# Adafruit_Sparkle_Motion_Stick.net
KiCad netlist of a schematic drawn in EAGLE
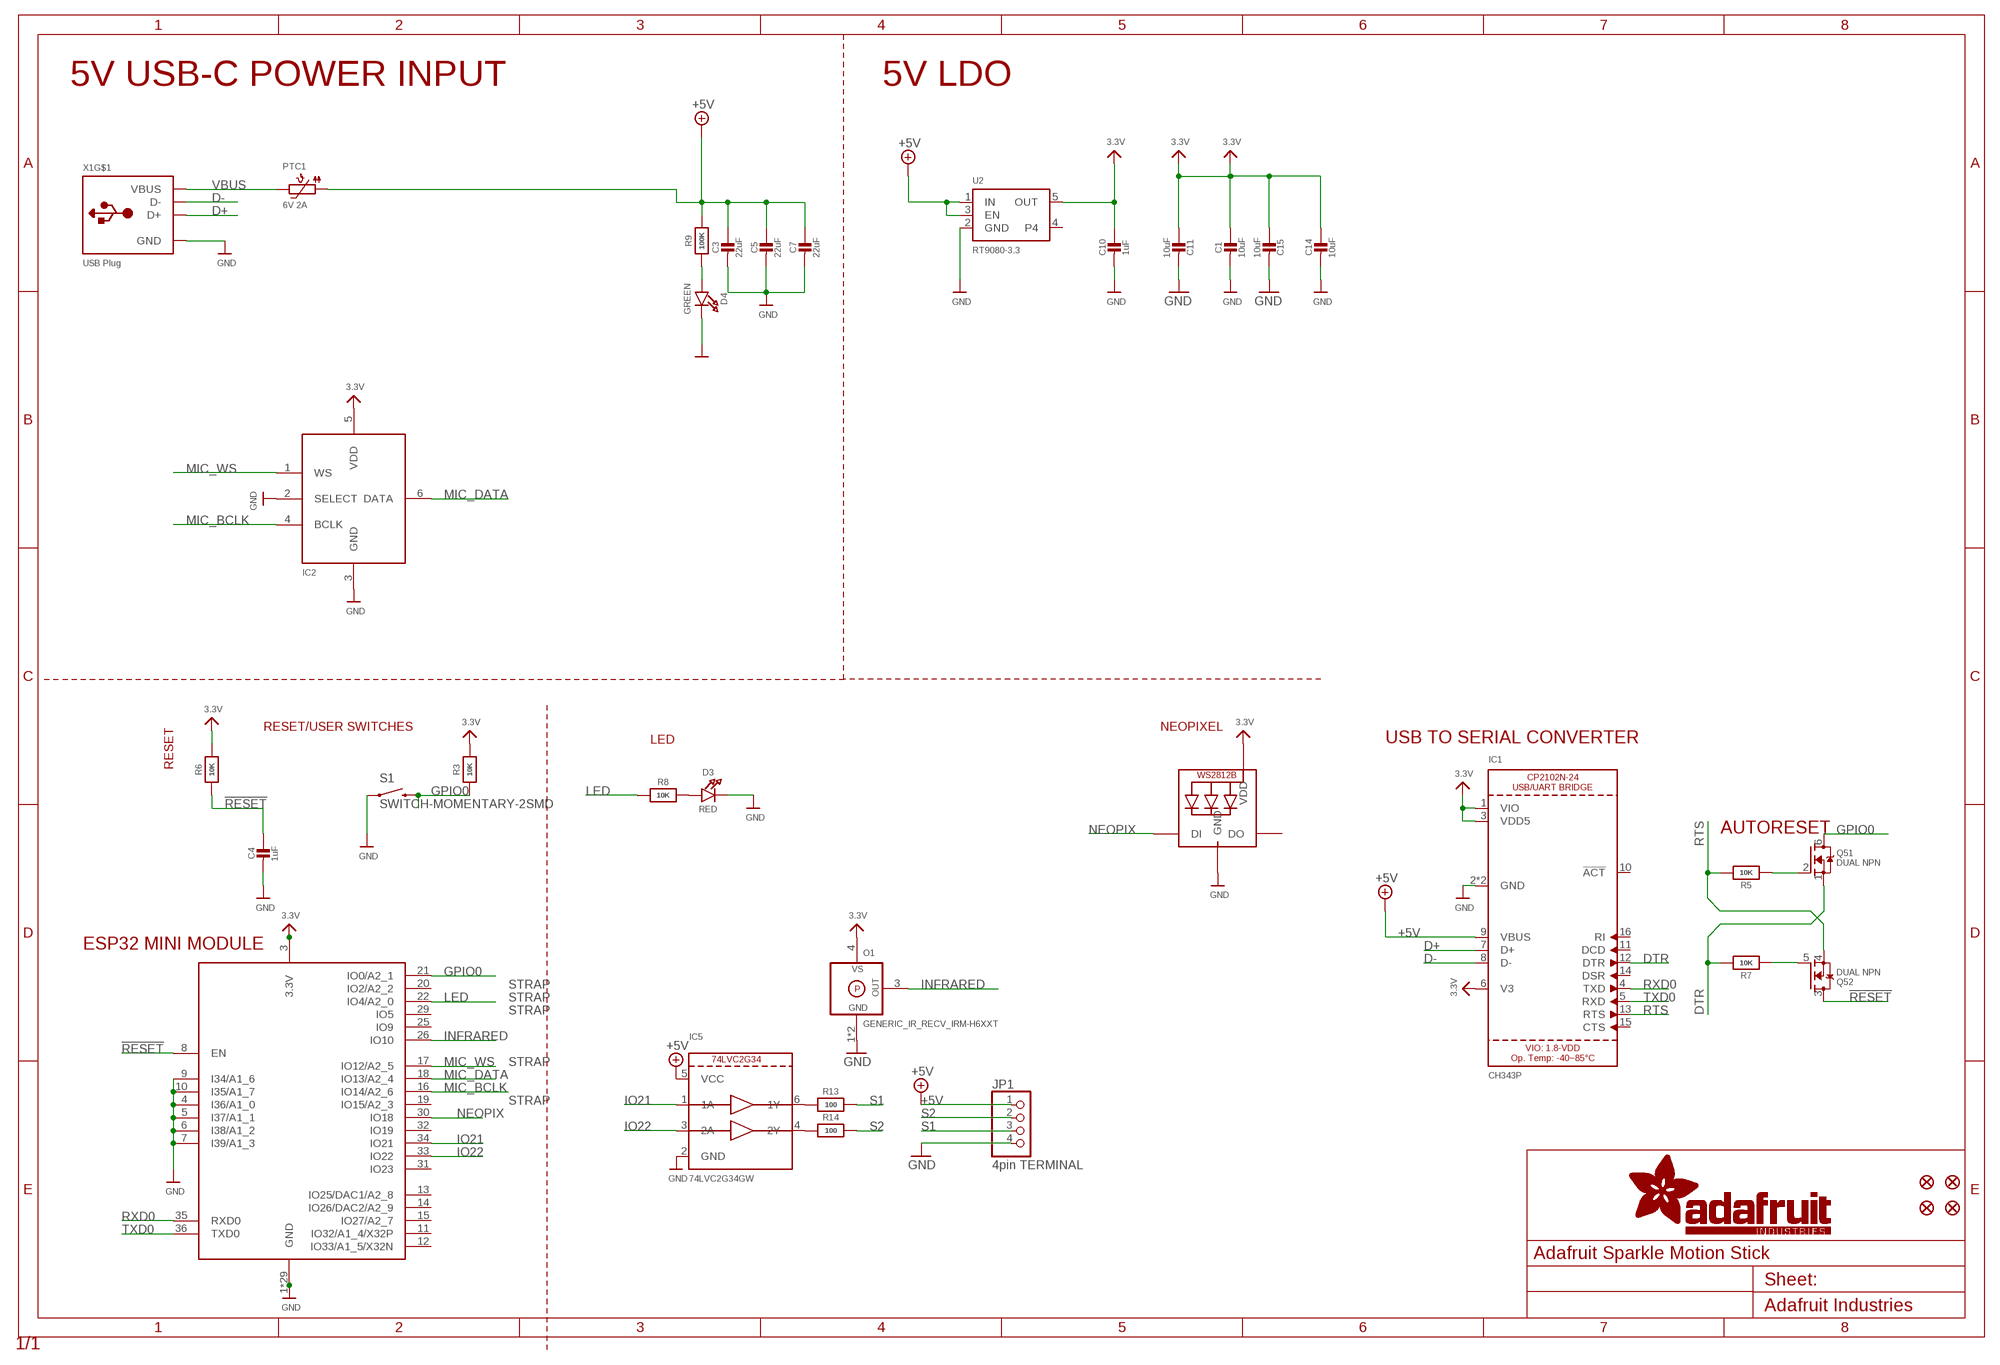
[diagram p0: schematic, sheet 1]

(export (version "E")
  (design (tool "Eeschema 10.0.6"))
  (components
    (comp (ref "C1")
      (value "10uF")
      (footprint "eagle-import:0805-NO")
      (libsource (lib "eagle-import") (part "CAP_CERAMIC0805-NOOUTLINE"))
    )
    (comp (ref "C3")
      (value "22uF")
      (footprint "eagle-import:0805-NO")
      (libsource (lib "eagle-import") (part "CAP_CERAMIC0805-NOOUTLINE"))
    )
    (comp (ref "C4")
      (value "1uF")
      (footprint "eagle-import:0603-NO")
      (libsource (lib "eagle-import") (part "CAP_CERAMIC0603_NO"))
    )
    (comp (ref "C5")
      (value "22uF")
      (footprint "eagle-import:0805-NO")
      (libsource (lib "eagle-import") (part "CAP_CERAMIC0805-NOOUTLINE"))
    )
    (comp (ref "C7")
      (value "22uF")
      (footprint "eagle-import:0805-NO")
      (libsource (lib "eagle-import") (part "CAP_CERAMIC0805-NOOUTLINE"))
    )
    (comp (ref "C10")
      (value "1uF")
      (footprint "eagle-import:0603-NO")
      (libsource (lib "eagle-import") (part "CAP_CERAMIC0603_NO"))
    )
    (comp (ref "C11")
      (value "10uF")
      (footprint "eagle-import:0805-NO")
      (libsource (lib "eagle-import") (part "CAP_CERAMIC0805-NOOUTLINE"))
    )
    (comp (ref "C14")
      (value "10uF")
      (footprint "eagle-import:0805-NO")
      (libsource (lib "eagle-import") (part "CAP_CERAMIC0805-NOOUTLINE"))
    )
    (comp (ref "C15")
      (value "10uF")
      (footprint "eagle-import:0805-NO")
      (libsource (lib "eagle-import") (part "CAP_CERAMIC0805-NOOUTLINE"))
    )
    (comp (ref "D3")
      (value "RED")
      (footprint "eagle-import:CHIPLED_0603_NOOUTLINE")
      (libsource (lib "eagle-import") (part "LED0603_NOOUTLINE"))
    )
    (comp (ref "D4")
      (value "GREEN")
      (footprint "eagle-import:CHIPLED_0603_NOOUTLINE")
      (libsource (lib "eagle-import") (part "LED0603_NOOUTLINE"))
    )
    (comp (ref "IC1")
      (value "CH343P")
      (footprint "eagle-import:QFN16_3MM")
      (libsource (lib "eagle-import") (part "CH343P"))
    )
    (comp (ref "IC2")
      (value "ICS-43434")
      (footprint "eagle-import:SPH0645LM4H")
      (libsource (lib "eagle-import") (part "MIC_I2S_SPH0645"))
    )
    (comp (ref "IC5")
      (value "74LVC2G34GW")
      (footprint "eagle-import:SC70-6L")
      (libsource (lib "eagle-import") (part "74LVC2G34GW"))
    )
    (comp (ref "JP1")
      (value "4pin TERMINAL")
      (footprint "eagle-import:1X04_2.54MMTERMINAL")
      (libsource (lib "eagle-import") (part "HEADER-1X4_254MMTERM"))
    )
    (comp (ref "LED1")
      (value "WS2812B_SK6805_1515")
      (footprint "eagle-import:SK6805_1515")
      (libsource (lib "eagle-import") (part "WS2812B_SK6805_1515"))
    )
    (comp (ref "O1")
      (value "GENERIC_IR_RECV_IRM-H6XXT")
      (footprint "eagle-import:IRM-H6XXT")
      (libsource (lib "eagle-import") (part "GENERIC_IR_RECV_IRM-H6XXT"))
    )
    (comp (ref "PTC1")
      (value "6V 2A")
      (footprint "eagle-import:0805-NO")
      (libsource (lib "eagle-import") (part "PTC_0805"))
    )
    (comp (ref "Q5")
      (value "DUAL NPN")
      (footprint "eagle-import:SOT363")
      (fields (field (name "JLC_ROTATION") "90"))
      (libsource (lib "eagle-import") (part "MOSFET-N_DUAL"))
    )
    (comp (ref "R3")
      (value "10K")
      (footprint "eagle-import:0603-NO")
      (libsource (lib "eagle-import") (part "RESISTOR_0603_NOOUT"))
    )
    (comp (ref "R5")
      (value "10K")
      (footprint "eagle-import:0603-NO")
      (libsource (lib "eagle-import") (part "RESISTOR_0603_NOOUT"))
    )
    (comp (ref "R6")
      (value "10K")
      (footprint "eagle-import:0603-NO")
      (libsource (lib "eagle-import") (part "RESISTOR_0603_NOOUT"))
    )
    (comp (ref "R7")
      (value "10K")
      (footprint "eagle-import:0603-NO")
      (libsource (lib "eagle-import") (part "RESISTOR_0603_NOOUT"))
    )
    (comp (ref "R8")
      (value "10K")
      (footprint "eagle-import:0603-NO")
      (libsource (lib "eagle-import") (part "RESISTOR_0603_NOOUT"))
    )
    (comp (ref "R9")
      (value "100K")
      (footprint "eagle-import:0603-NO")
      (libsource (lib "eagle-import") (part "RESISTOR_0603_NOOUT"))
    )
    (comp (ref "R13")
      (value "100")
      (footprint "eagle-import:0603-NO")
      (libsource (lib "eagle-import") (part "RESISTOR_0603_NOOUT"))
    )
    (comp (ref "R14")
      (value "100")
      (footprint "eagle-import:0603-NO")
      (libsource (lib "eagle-import") (part "RESISTOR_0603_NOOUT"))
    )
    (comp (ref "S1")
      (value "SWITCH-MOMENTARY-2SMD")
      (footprint "eagle-import:TACTILE_SWITCH_SMD")
      (libsource (lib "eagle-import") (part "SWITCH-MOMENTARY-2SMD"))
    )
    (comp (ref "U$23")
      (value "FIDUCIAL_0.5MM")
      (footprint "eagle-import:FIDUCIAL_0.5MM")
      (libsource (lib "eagle-import") (part "FIDUCIAL_0.5MM"))
    )
    (comp (ref "U$25")
      (value "FIDUCIAL_0.5MM")
      (footprint "eagle-import:FIDUCIAL_0.5MM")
      (libsource (lib "eagle-import") (part "FIDUCIAL_0.5MM"))
    )
    (comp (ref "U$34")
      (value "FIDUCIAL_0.5MM")
      (footprint "eagle-import:FIDUCIAL_0.5MM")
      (libsource (lib "eagle-import") (part "FIDUCIAL_0.5MM"))
    )
    (comp (ref "U$35")
      (value "FIDUCIAL_0.5MM")
      (footprint "eagle-import:FIDUCIAL_0.5MM")
      (libsource (lib "eagle-import") (part "FIDUCIAL_0.5MM"))
    )
    (comp (ref "U2")
      (value "RT9080-3.3")
      (footprint "eagle-import:SOT23-5")
      (fields (field (name "JLC_ROTATION") "0"))
      (libsource (lib "eagle-import") (part "VREG_SOT23-5"))
    )
    (comp (ref "X1")
      (value "USB Plug")
      (footprint "eagle-import:USB_A-UGO4DD")
      (libsource (lib "eagle-import") (part "USB_TYPEA_UG04DD"))
    )
    (comp (ref "X4")
      (value "ESP32-MINI-1")
      (footprint "eagle-import:ESP32-MINI-1")
      (libsource (lib "eagle-import") (part "ESP32-MINI-1"))
    )
  )
  (nets
    (net (code "1") (name "+5V") (class "Default")
      (node (ref "C3") (pin "1") (pinfunction "1_1") (pintype "passive"))
      (node (ref "C5") (pin "1") (pinfunction "1_1") (pintype "passive"))
      (node (ref "C7") (pin "1") (pinfunction "1_1") (pintype "passive"))
      (node (ref "IC1") (pin "9") (pinfunction "VBUS_9") (pintype "power_in"))
      (node (ref "IC5") (pin "5") (pinfunction "VCC_5") (pintype "power_in"))
      (node (ref "JP1") (pin "1") (pinfunction "1_1") (pintype "passive"))
      (node (ref "PTC1") (pin "1") (pinfunction "1_1") (pintype "passive"))
      (node (ref "R9") (pin "2") (pinfunction "2_2") (pintype "passive"))
      (node (ref "U2") (pin "1") (pinfunction "IN_1") (pintype "power_in"))
      (node (ref "U2") (pin "3") (pinfunction "EN_3") (pintype "input"))
    )
    (net (code "2") (name "/D+") (class "Default")
      (node (ref "IC1") (pin "7") (pinfunction "D+_7") (pintype "bidirectional"))
      (node (ref "X1") (pin "D+") (pinfunction "D+_D+") (pintype "bidirectional"))
    )
    (net (code "3") (name "/D-") (class "Default")
      (node (ref "IC1") (pin "8") (pinfunction "D-_8") (pintype "bidirectional"))
      (node (ref "X1") (pin "D-") (pinfunction "D-_D-") (pintype "bidirectional"))
    )
    (net (code "4") (name "/DTR") (class "Default")
      (node (ref "IC1") (pin "12") (pinfunction "DTR_12") (pintype "output"))
      (node (ref "Q5") (pin "1") (pinfunction "S_1") (pintype "bidirectional"))
      (node (ref "R7") (pin "2") (pinfunction "2_2") (pintype "passive"))
    )
    (net (code "5") (name "/GPIO0") (class "Default")
      (node (ref "Q5") (pin "6") (pinfunction "D_6") (pintype "bidirectional"))
      (node (ref "R3") (pin "1") (pinfunction "1_1") (pintype "passive"))
      (node (ref "S1") (pin "3") (pinfunction "2_3") (pintype "passive"))
      (node (ref "X4") (pin "21") (pinfunction "IO0/A2_1_21") (pintype "bidirectional"))
    )
    (net (code "6") (name "/INFRARED") (class "Default")
      (node (ref "O1") (pin "3") (pinfunction "OUT_3") (pintype "output"))
      (node (ref "X4") (pin "26") (pinfunction "IO10_26") (pintype "bidirectional"))
    )
    (net (code "7") (name "/IO21") (class "Default")
      (node (ref "IC5") (pin "1") (pinfunction "1A_1") (pintype "input"))
      (node (ref "X4") (pin "34") (pinfunction "IO21_34") (pintype "bidirectional"))
    )
    (net (code "8") (name "/IO22") (class "Default")
      (node (ref "IC5") (pin "3") (pinfunction "2A_3") (pintype "input"))
      (node (ref "X4") (pin "33") (pinfunction "IO22_33") (pintype "bidirectional"))
    )
    (net (code "9") (name "/LED") (class "Default")
      (node (ref "R8") (pin "1") (pinfunction "1_1") (pintype "passive"))
      (node (ref "X4") (pin "22") (pinfunction "IO4/A2_0_22") (pintype "bidirectional"))
    )
    (net (code "10") (name "/MIC_BCLK") (class "Default")
      (node (ref "IC2") (pin "4") (pinfunction "BCLK_4") (pintype "input"))
      (node (ref "X4") (pin "16") (pinfunction "IO14/A2_6_16") (pintype "bidirectional"))
    )
    (net (code "11") (name "/MIC_DATA") (class "Default")
      (node (ref "IC2") (pin "6") (pinfunction "DATA_6") (pintype "output"))
      (node (ref "X4") (pin "18") (pinfunction "IO13/A2_4_18") (pintype "bidirectional"))
    )
    (net (code "12") (name "/MIC_WS") (class "Default")
      (node (ref "IC2") (pin "1") (pinfunction "WS_1") (pintype "input"))
      (node (ref "X4") (pin "17") (pinfunction "IO12/A2_5_17") (pintype "bidirectional"))
    )
    (net (code "13") (name "/NEOPIX") (class "Default")
      (node (ref "LED1") (pin "1") (pinfunction "DI_1") (pintype "input"))
      (node (ref "X4") (pin "30") (pinfunction "IO18_30") (pintype "bidirectional"))
    )
    (net (code "14") (name "/RTS") (class "Default")
      (node (ref "IC1") (pin "13") (pinfunction "RTS_13") (pintype "output"))
      (node (ref "Q5") (pin "4") (pinfunction "S_4") (pintype "bidirectional"))
      (node (ref "R5") (pin "2") (pinfunction "2_2") (pintype "passive"))
    )
    (net (code "15") (name "/RXD0") (class "Default")
      (node (ref "IC1") (pin "4") (pinfunction "TXD_4") (pintype "output"))
      (node (ref "X4") (pin "35") (pinfunction "RXD0_35") (pintype "input"))
    )
    (net (code "16") (name "/S1") (class "Default")
      (node (ref "JP1") (pin "3") (pinfunction "3_3") (pintype "passive"))
      (node (ref "R13") (pin "2") (pinfunction "2_2") (pintype "passive"))
    )
    (net (code "17") (name "/S2") (class "Default")
      (node (ref "JP1") (pin "2") (pinfunction "2_2") (pintype "passive"))
      (node (ref "R14") (pin "2") (pinfunction "2_2") (pintype "passive"))
    )
    (net (code "18") (name "/TXD0") (class "Default")
      (node (ref "IC1") (pin "5") (pinfunction "RXD_5") (pintype "input"))
      (node (ref "X4") (pin "36") (pinfunction "TXD0_36") (pintype "output"))
    )
    (net (code "19") (name "/VBUS") (class "Default")
      (node (ref "PTC1") (pin "2") (pinfunction "2_2") (pintype "passive"))
      (node (ref "X1") (pin "VBUS") (pinfunction "VBUS_VBUS") (pintype "power_in"))
    )
    (net (code "20") (name "/~{RESET}") (class "Default")
      (node (ref "C4") (pin "1") (pinfunction "1_1") (pintype "passive"))
      (node (ref "Q5") (pin "3") (pinfunction "D_3") (pintype "bidirectional"))
      (node (ref "R6") (pin "1") (pinfunction "1_1") (pintype "passive"))
      (node (ref "X4") (pin "8") (pinfunction "EN_8") (pintype "input"))
    )
    (net (code "21") (name "3.3V") (class "Default")
      (node (ref "C1") (pin "1") (pinfunction "1_1") (pintype "passive"))
      (node (ref "C10") (pin "1") (pinfunction "1_1") (pintype "passive"))
      (node (ref "C11") (pin "1") (pinfunction "1_1") (pintype "passive"))
      (node (ref "C14") (pin "1") (pinfunction "1_1") (pintype "passive"))
      (node (ref "C15") (pin "1") (pinfunction "1_1") (pintype "passive"))
      (node (ref "IC1") (pin "1") (pinfunction "VIO_1") (pintype "power_in"))
      (node (ref "IC1") (pin "3") (pinfunction "VDD5_3") (pintype "power_in"))
      (node (ref "IC1") (pin "6") (pinfunction "V3_6") (pintype "passive"))
      (node (ref "IC2") (pin "5") (pinfunction "VDD_5") (pintype "power_in"))
      (node (ref "LED1") (pin "2") (pinfunction "VDD_2") (pintype "power_in"))
      (node (ref "O1") (pin "4") (pinfunction "VS_4") (pintype "power_in"))
      (node (ref "R3") (pin "2") (pinfunction "2_2") (pintype "passive"))
      (node (ref "R6") (pin "2") (pinfunction "2_2") (pintype "passive"))
      (node (ref "U2") (pin "5") (pinfunction "OUT_5") (pintype "power_in"))
      (node (ref "X4") (pin "3") (pinfunction "3.3V_3") (pintype "passive"))
    )
    (net (code "22") (name "GND") (class "Default")
      (node (ref "C1") (pin "2") (pinfunction "2_2") (pintype "passive"))
      (node (ref "C10") (pin "2") (pinfunction "2_2") (pintype "passive"))
      (node (ref "C11") (pin "2") (pinfunction "2_2") (pintype "passive"))
      (node (ref "C14") (pin "2") (pinfunction "2_2") (pintype "passive"))
      (node (ref "C15") (pin "2") (pinfunction "2_2") (pintype "passive"))
      (node (ref "C3") (pin "2") (pinfunction "2_2") (pintype "passive"))
      (node (ref "C4") (pin "2") (pinfunction "2_2") (pintype "passive"))
      (node (ref "C5") (pin "2") (pinfunction "2_2") (pintype "passive"))
      (node (ref "C7") (pin "2") (pinfunction "2_2") (pintype "passive"))
      (node (ref "D3") (pin "C") (pinfunction "C_C") (pintype "passive"))
      (node (ref "D4") (pin "C") (pinfunction "C_C") (pintype "passive"))
      (node (ref "IC1") (pin "2") (pinfunction "GND_2") (pintype "power_in"))
      (node (ref "IC1") (pin "THERMAL") (pinfunction "GND_THERMAL") (pintype "power_in"))
      (node (ref "IC2") (pin "2") (pinfunction "SELECT_2") (pintype "input"))
      (node (ref "IC2") (pin "3") (pinfunction "GND_3") (pintype "power_in"))
      (node (ref "IC5") (pin "2") (pinfunction "GND_2") (pintype "power_in"))
      (node (ref "JP1") (pin "4") (pinfunction "4_4") (pintype "passive"))
      (node (ref "LED1") (pin "4") (pinfunction "GND_4") (pintype "power_in"))
      (node (ref "O1") (pin "1") (pinfunction "GND_1") (pintype "power_in"))
      (node (ref "O1") (pin "2") (pinfunction "GND_2") (pintype "power_in"))
      (node (ref "S1") (pin "1") (pinfunction "1_1") (pintype "passive"))
      (node (ref "U2") (pin "2") (pinfunction "GND_2") (pintype "power_in"))
      (node (ref "X1") (pin "GND") (pinfunction "GND_GND") (pintype "power_in"))
      (node (ref "X4") (pin "1") (pinfunction "GND_1") (pintype "passive"))
      (node (ref "X4") (pin "10") (pinfunction "I35/A1_7_10") (pintype "input"))
      (node (ref "X4") (pin "2") (pinfunction "GND_2") (pintype "passive"))
      (node (ref "X4") (pin "27") (pinfunction "GND_27") (pintype "passive"))
      (node (ref "X4") (pin "38") (pinfunction "GND_38") (pintype "passive"))
      (node (ref "X4") (pin "39") (pinfunction "GND_39") (pintype "passive"))
      (node (ref "X4") (pin "4") (pinfunction "I36/A1_0_4") (pintype "input"))
      (node (ref "X4") (pin "40") (pinfunction "GND_40") (pintype "passive"))
      (node (ref "X4") (pin "41") (pinfunction "GND_41") (pintype "passive"))
      (node (ref "X4") (pin "42") (pinfunction "GND_42") (pintype "passive"))
      (node (ref "X4") (pin "43") (pinfunction "GND_43") (pintype "passive"))
      (node (ref "X4") (pin "44") (pinfunction "GND_44") (pintype "passive"))
      (node (ref "X4") (pin "45") (pinfunction "GND_45") (pintype "passive"))
      (node (ref "X4") (pin "46") (pinfunction "GND_46") (pintype "passive"))
      (node (ref "X4") (pin "47") (pinfunction "GND_47") (pintype "passive"))
      (node (ref "X4") (pin "48") (pinfunction "GND_48") (pintype "passive"))
      (node (ref "X4") (pin "49") (pinfunction "GND_49") (pintype "passive"))
      (node (ref "X4") (pin "5") (pinfunction "I37/A1_1_5") (pintype "input"))
      (node (ref "X4") (pin "50") (pinfunction "GND_50") (pintype "passive"))
      (node (ref "X4") (pin "51") (pinfunction "GND_51") (pintype "passive"))
      (node (ref "X4") (pin "52") (pinfunction "GND_52") (pintype "passive"))
      (node (ref "X4") (pin "53") (pinfunction "GND_53") (pintype "passive"))
      (node (ref "X4") (pin "54") (pinfunction "GND_54") (pintype "passive"))
      (node (ref "X4") (pin "55") (pinfunction "GND_55") (pintype "passive"))
      (node (ref "X4") (pin "56") (pinfunction "GND_56") (pintype "passive"))
      (node (ref "X4") (pin "57") (pinfunction "GND_57") (pintype "passive"))
      (node (ref "X4") (pin "58") (pinfunction "GND_58") (pintype "passive"))
      (node (ref "X4") (pin "59") (pinfunction "GND_59") (pintype "passive"))
      (node (ref "X4") (pin "6") (pinfunction "I38/A1_2_6") (pintype "input"))
      (node (ref "X4") (pin "60") (pinfunction "GND_60") (pintype "passive"))
      (node (ref "X4") (pin "61") (pinfunction "GND_61") (pintype "passive"))
      (node (ref "X4") (pin "62") (pinfunction "GND_62") (pintype "passive"))
      (node (ref "X4") (pin "63") (pinfunction "GND_63") (pintype "passive"))
      (node (ref "X4") (pin "7") (pinfunction "I39/A1_3_7") (pintype "input"))
      (node (ref "X4") (pin "9") (pinfunction "I34/A1_6_9") (pintype "input"))
    )
    (net (code "23") (name "Net-(D3-PadA)") (class "Default")
      (node (ref "D3") (pin "A") (pinfunction "A_A") (pintype "passive"))
      (node (ref "R8") (pin "2") (pinfunction "2_2") (pintype "passive"))
    )
    (net (code "24") (name "Net-(D4-PadA)") (class "Default")
      (node (ref "D4") (pin "A") (pinfunction "A_A") (pintype "passive"))
      (node (ref "R9") (pin "1") (pinfunction "1_1") (pintype "passive"))
    )
    (net (code "25") (name "Net-(IC5-1Y)") (class "Default")
      (node (ref "IC5") (pin "6") (pinfunction "1Y_6") (pintype "output"))
      (node (ref "R13") (pin "1") (pinfunction "1_1") (pintype "passive"))
    )
    (net (code "26") (name "Net-(IC5-2Y)") (class "Default")
      (node (ref "IC5") (pin "4") (pinfunction "2Y_4") (pintype "output"))
      (node (ref "R14") (pin "1") (pinfunction "1_1") (pintype "passive"))
    )
    (net (code "27") (name "Net-(Q5A-G)") (class "Default")
      (node (ref "Q5") (pin "2") (pinfunction "G_2") (pintype "bidirectional"))
      (node (ref "R5") (pin "1") (pinfunction "1_1") (pintype "passive"))
    )
    (net (code "28") (name "Net-(Q5B-G)") (class "Default")
      (node (ref "Q5") (pin "5") (pinfunction "G_5") (pintype "bidirectional"))
      (node (ref "R7") (pin "1") (pinfunction "1_1") (pintype "passive"))
    )
    (net (code "29") (name "unconnected-(IC1-CTS-Pad15)") (class "Default")
      (node (ref "IC1") (pin "15") (pinfunction "CTS_15") (pintype "input"))
    )
    (net (code "30") (name "unconnected-(IC1-DCD-Pad11)") (class "Default")
      (node (ref "IC1") (pin "11") (pinfunction "DCD_11") (pintype "input"))
    )
    (net (code "31") (name "unconnected-(IC1-DSR-Pad14)") (class "Default")
      (node (ref "IC1") (pin "14") (pinfunction "DSR_14") (pintype "input"))
    )
    (net (code "32") (name "unconnected-(IC1-RI-Pad16)") (class "Default")
      (node (ref "IC1") (pin "16") (pinfunction "RI_16") (pintype "input"))
    )
    (net (code "33") (name "unconnected-(IC1-~{ACT}-Pad10)") (class "Default")
      (node (ref "IC1") (pin "10") (pinfunction "~{ACT}_10") (pintype "bidirectional"))
    )
    (net (code "34") (name "unconnected-(LED1-DO-Pad3)") (class "Default")
      (node (ref "LED1") (pin "3") (pinfunction "DO_3") (pintype "output"))
    )
    (net (code "35") (name "unconnected-(U2-P4-Pad4)") (class "Default")
      (node (ref "U2") (pin "4") (pinfunction "P4_4") (pintype "bidirectional"))
    )
    (net (code "36") (name "unconnected-(X4-IO2{slash}A2_2-Pad20)") (class "Default")
      (node (ref "X4") (pin "20") (pinfunction "IO2/A2_2_20") (pintype "bidirectional"))
    )
    (net (code "37") (name "unconnected-(X4-IO5-Pad29)") (class "Default")
      (node (ref "X4") (pin "29") (pinfunction "IO5_29") (pintype "bidirectional"))
    )
    (net (code "38") (name "unconnected-(X4-IO9-Pad25)") (class "Default")
      (node (ref "X4") (pin "25") (pinfunction "IO9_25") (pintype "bidirectional"))
    )
    (net (code "39") (name "unconnected-(X4-IO15{slash}A2_3-Pad19)") (class "Default")
      (node (ref "X4") (pin "19") (pinfunction "IO15/A2_3_19") (pintype "bidirectional"))
    )
    (net (code "40") (name "unconnected-(X4-IO19-Pad32)") (class "Default")
      (node (ref "X4") (pin "32") (pinfunction "IO19_32") (pintype "bidirectional"))
    )
    (net (code "41") (name "unconnected-(X4-IO23-Pad31)") (class "Default")
      (node (ref "X4") (pin "31") (pinfunction "IO23_31") (pintype "bidirectional"))
    )
    (net (code "42") (name "unconnected-(X4-IO25{slash}DAC1{slash}A2_8-Pad13)") (class "Default")
      (node (ref "X4") (pin "13") (pinfunction "IO25/DAC1/A2_8_13") (pintype "bidirectional"))
    )
    (net (code "43") (name "unconnected-(X4-IO26{slash}DAC2{slash}A2_9-Pad14)") (class "Default")
      (node (ref "X4") (pin "14") (pinfunction "IO26/DAC2/A2_9_14") (pintype "bidirectional"))
    )
    (net (code "44") (name "unconnected-(X4-IO27{slash}A2_7-Pad15)") (class "Default")
      (node (ref "X4") (pin "15") (pinfunction "IO27/A2_7_15") (pintype "bidirectional"))
    )
    (net (code "45") (name "unconnected-(X4-IO32{slash}A1_4{slash}X32P-Pad11)") (class "Default")
      (node (ref "X4") (pin "11") (pinfunction "IO32/A1_4/X32P_11") (pintype "bidirectional"))
    )
    (net (code "46") (name "unconnected-(X4-IO33{slash}A1_5{slash}X32N-Pad12)") (class "Default")
      (node (ref "X4") (pin "12") (pinfunction "IO33/A1_5/X32N_12") (pintype "bidirectional"))
    )
  )
)
